# ospi160.net
KiCad netlist of a schematic drawn in EAGLE
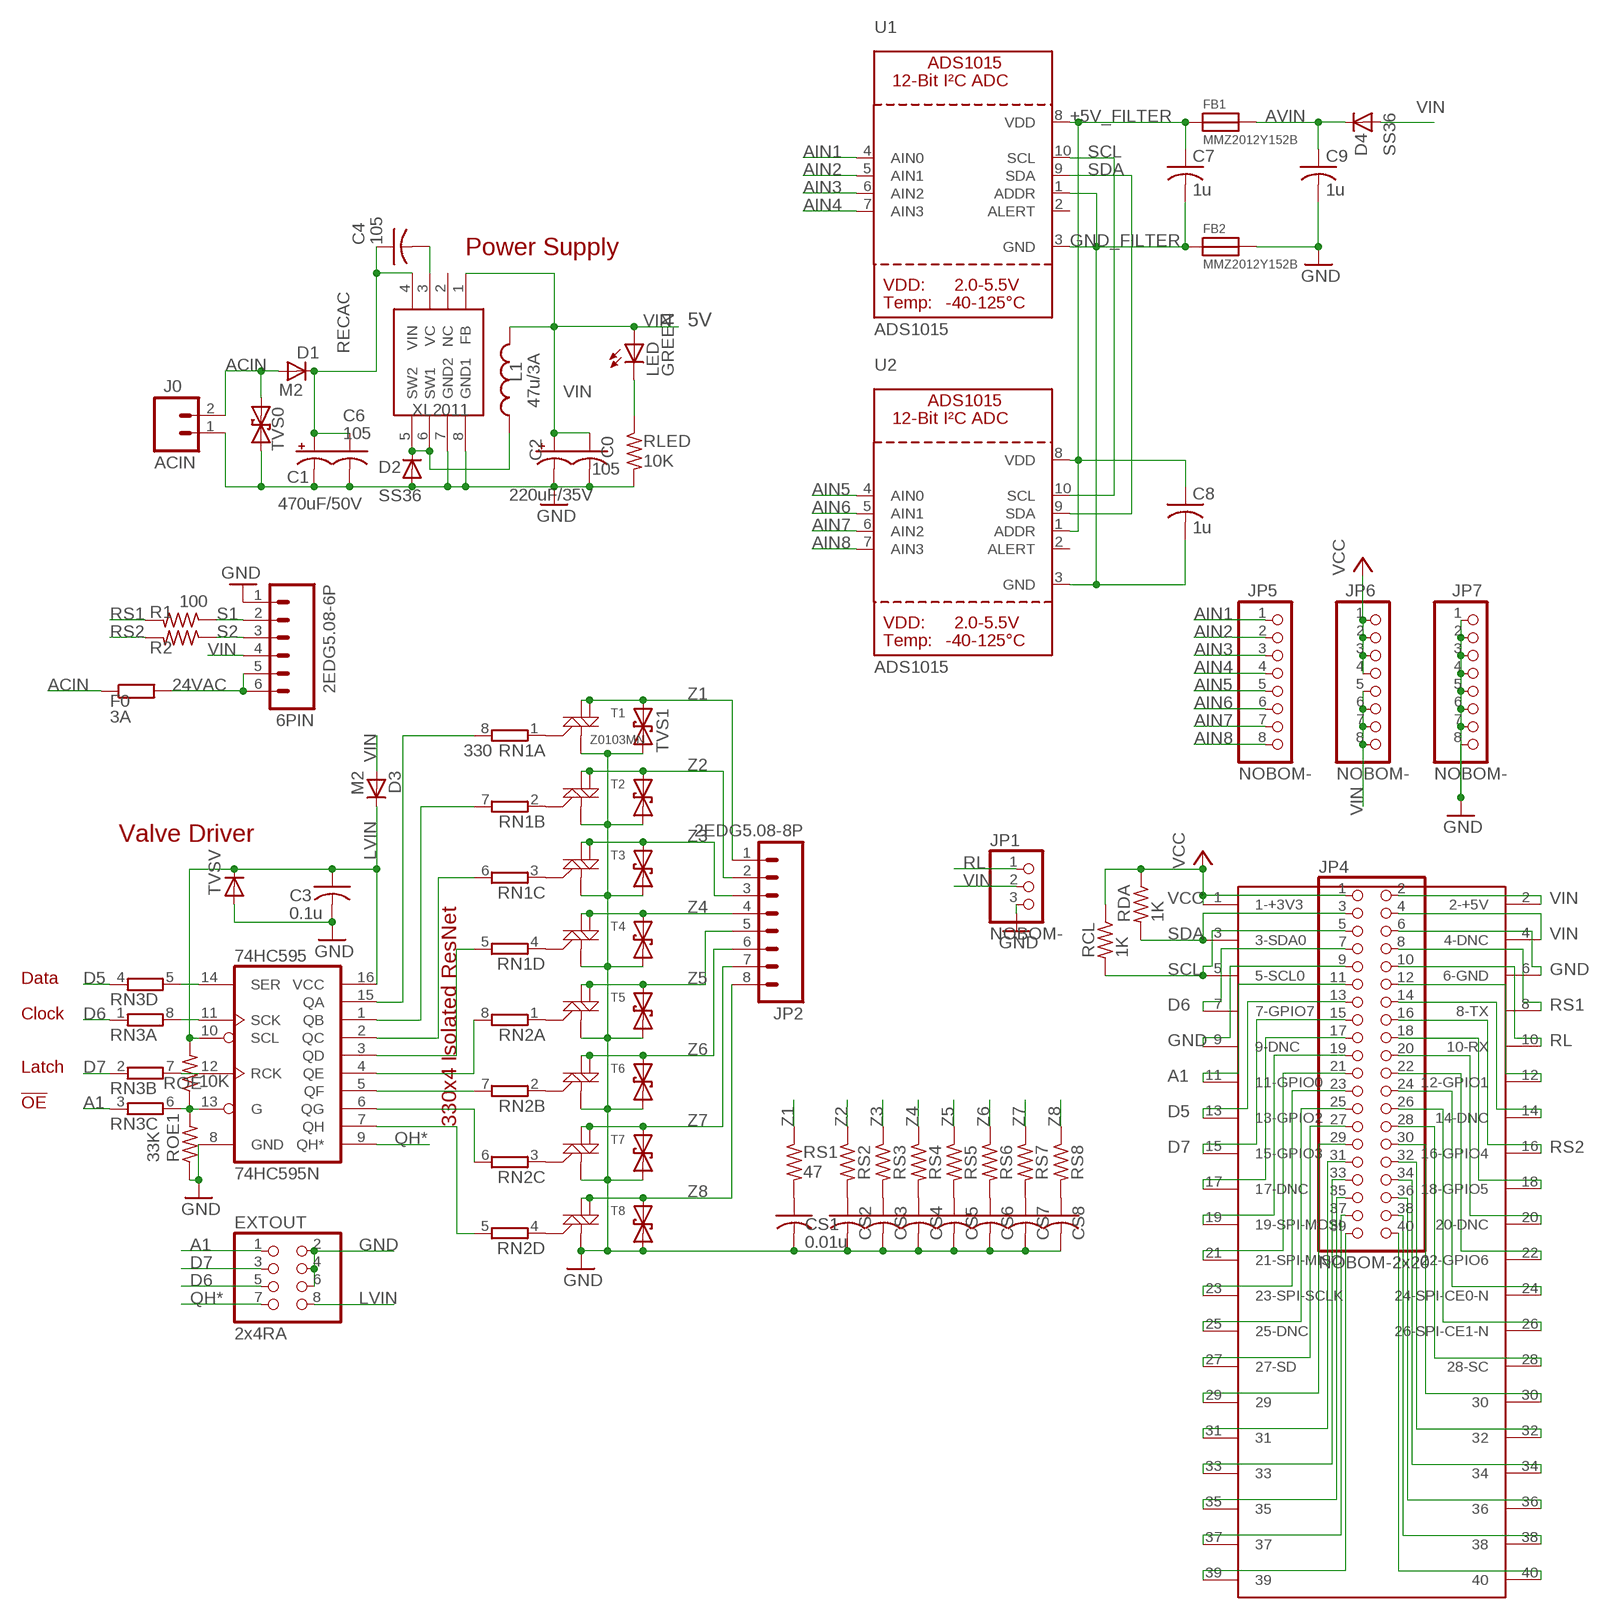
[diagram p0: schematic, sheet 1]

(export (version "E")
  (design (tool "Eeschema 10.0.6"))
  (components
    (comp (ref "6PIN")
      (value "2EDG5.08-6P")
      (footprint "eagle-import:SCREWTERMINAL-5MM-6")
      (libsource (lib "eagle-import") (part "M065MM"))
    )
    (comp (ref "74HC595")
      (value "74HC595N")
      (footprint "eagle-import:SO16")
      (libsource (lib "eagle-import") (part "74595DLS"))
    )
    (comp (ref "C0")
      (value "105")
      (footprint "eagle-import:C0603K")
      (libsource (lib "eagle-import") (part "C-USC0603K"))
    )
    (comp (ref "C1")
      (value "470uF/50V")
      (footprint "eagle-import:E5-10,5")
      (libsource (lib "eagle-import") (part "CPOL-USE5-10.5"))
    )
    (comp (ref "C2")
      (value "220uF/35V")
      (footprint "eagle-import:E3,5-8")
      (libsource (lib "eagle-import") (part "CPOL-USE3.5-8"))
    )
    (comp (ref "C3")
      (value "0.1u")
      (footprint "eagle-import:C0603K")
      (libsource (lib "eagle-import") (part "C-USC0603K"))
    )
    (comp (ref "C4")
      (value "105")
      (footprint "eagle-import:C0603K")
      (libsource (lib "eagle-import") (part "C-USC0603K"))
    )
    (comp (ref "C6")
      (value "105")
      (footprint "eagle-import:C0603K")
      (libsource (lib "eagle-import") (part "C-USC0603K"))
    )
    (comp (ref "C7")
      (value "1u")
      (footprint "eagle-import:C0603K")
      (libsource (lib "eagle-import") (part "adafruit2013_C-USC0603K"))
    )
    (comp (ref "C8")
      (value "1u")
      (footprint "eagle-import:C0603K")
      (libsource (lib "eagle-import") (part "adafruit2013_C-USC0603K"))
    )
    (comp (ref "C9")
      (value "1u")
      (footprint "eagle-import:C0603K")
      (libsource (lib "eagle-import") (part "adafruit2013_C-USC0603K"))
    )
    (comp (ref "CS1")
      (value "0.01u")
      (footprint "eagle-import:C0603K")
      (libsource (lib "eagle-import") (part "C-USC0603K"))
    )
    (comp (ref "CS2")
      (value "0.01u")
      (footprint "eagle-import:C0603K")
      (libsource (lib "eagle-import") (part "C-USC0603K"))
    )
    (comp (ref "CS3")
      (value "0.01u")
      (footprint "eagle-import:C0603K")
      (libsource (lib "eagle-import") (part "C-USC0603K"))
    )
    (comp (ref "CS4")
      (value "0.01u")
      (footprint "eagle-import:C0603K")
      (libsource (lib "eagle-import") (part "C-USC0603K"))
    )
    (comp (ref "CS5")
      (value "0.01u")
      (footprint "eagle-import:C0603K")
      (libsource (lib "eagle-import") (part "C-USC0603K"))
    )
    (comp (ref "CS6")
      (value "0.01u")
      (footprint "eagle-import:C0603K")
      (libsource (lib "eagle-import") (part "C-USC0603K"))
    )
    (comp (ref "CS7")
      (value "0.01u")
      (footprint "eagle-import:C0603K")
      (libsource (lib "eagle-import") (part "C-USC0603K"))
    )
    (comp (ref "CS8")
      (value "0.01u")
      (footprint "eagle-import:C0603K")
      (libsource (lib "eagle-import") (part "C-USC0603K"))
    )
    (comp (ref "D1")
      (value "M2")
      (footprint "eagle-import:DO-214AC")
      (libsource (lib "eagle-import") (part "DIODE-DO-214AC"))
    )
    (comp (ref "D2")
      (value "SS36")
      (footprint "eagle-import:SMB")
      (libsource (lib "eagle-import") (part "DIODE-SMB"))
    )
    (comp (ref "D3")
      (value "M2")
      (footprint "eagle-import:DO-214AC")
      (libsource (lib "eagle-import") (part "DIODE-DO-214AC"))
    )
    (comp (ref "D4")
      (value "SS36")
      (footprint "eagle-import:SMB")
      (libsource (lib "eagle-import") (part "DIODE-SMB"))
    )
    (comp (ref "EXTOUT")
      (value "2x4RA")
      (footprint "eagle-import:2X04_90")
      (libsource (lib "eagle-import") (part "PINHD-2X4/90"))
    )
    (comp (ref "F0")
      (value "3A")
      (footprint "eagle-import:0207_15")
      (libsource (lib "eagle-import") (part "R-EU_0207/15"))
    )
    (comp (ref "FB1")
      (value "MMZ2012Y152B")
      (footprint "eagle-import:0805")
      (libsource (lib "eagle-import") (part "FERRITE0805"))
    )
    (comp (ref "FB2")
      (value "MMZ2012Y152B")
      (footprint "eagle-import:0805")
      (libsource (lib "eagle-import") (part "FERRITE0805"))
    )
    (comp (ref "J0")
      (value "ACIN")
      (footprint "eagle-import:SCREWTERMINAL-4MM-2-X")
      (libsource (lib "eagle-import") (part "M024MM-X"))
    )
    (comp (ref "JP1")
      (value "NOBOM-")
      (footprint "eagle-import:1X03")
      (libsource (lib "eagle-import") (part "PINHD-1X3"))
    )
    (comp (ref "JP2")
      (value "2EDG5.08-8P")
      (footprint "eagle-import:SCREWTERMINAL-5MM-8")
      (libsource (lib "eagle-import") (part "M085MM-8"))
    )
    (comp (ref "JP4")
      (value "NOBOM-2x20")
      (footprint "eagle-import:2X20")
      (libsource (lib "eagle-import") (part "PINHD-2X20"))
    )
    (comp (ref "JP5")
      (value "NOBOM-")
      (footprint "eagle-import:1X08-CLEANBIG")
      (libsource (lib "eagle-import") (part "PINHD-1X8CLEANBIG"))
    )
    (comp (ref "JP6")
      (value "NOBOM-")
      (footprint "eagle-import:1X08-CLEANBIG")
      (libsource (lib "eagle-import") (part "PINHD-1X8CLEANBIG"))
    )
    (comp (ref "JP7")
      (value "NOBOM-")
      (footprint "eagle-import:1X08-CLEANBIG")
      (libsource (lib "eagle-import") (part "PINHD-1X8CLEANBIG"))
    )
    (comp (ref "L1")
      (value "47u/3A")
      (footprint "eagle-import:YT1014")
      (libsource (lib "eagle-import") (part "INDUCTORYT1014"))
    )
    (comp (ref "LED")
      (value "GREEN")
      (footprint "eagle-import:CHIPLED_0805")
      (libsource (lib "eagle-import") (part "LEDCHIPLED_0805"))
    )
    (comp (ref "R1")
      (value "100")
      (footprint "eagle-import:R0603")
      (libsource (lib "eagle-import") (part "R-US_R0603"))
    )
    (comp (ref "R2")
      (value "100")
      (footprint "eagle-import:R0603")
      (libsource (lib "eagle-import") (part "R-US_R0603"))
    )
    (comp (ref "RCL")
      (value "1K")
      (footprint "eagle-import:R0603")
      (libsource (lib "eagle-import") (part "R-US_R0603"))
    )
    (comp (ref "RDA")
      (value "1K")
      (footprint "eagle-import:R0603")
      (libsource (lib "eagle-import") (part "R-US_R0603"))
    )
    (comp (ref "RLED")
      (value "10K")
      (footprint "eagle-import:R0603")
      (libsource (lib "eagle-import") (part "R-US_R0603"))
    )
    (comp (ref "RN1")
      (value "330")
      (footprint "eagle-import:EXB38V")
      (libsource (lib "eagle-import") (part "4R-NEXB38V"))
    )
    (comp (ref "RN2")
      (value "330")
      (footprint "eagle-import:EXB38V")
      (libsource (lib "eagle-import") (part "4R-NEXB38V"))
    )
    (comp (ref "RN3")
      (value "330")
      (footprint "eagle-import:EXB38V")
      (libsource (lib "eagle-import") (part "4R-NEXB38V"))
    )
    (comp (ref "ROE")
      (value "10K")
      (footprint "eagle-import:R0603")
      (libsource (lib "eagle-import") (part "R-US_R0603"))
    )
    (comp (ref "ROE1")
      (value "33K")
      (footprint "eagle-import:R0603")
      (libsource (lib "eagle-import") (part "R-US_R0603"))
    )
    (comp (ref "RPI")
      (value "RPIB+B+")
      (footprint "eagle-import:RPIB+")
      (libsource (lib "eagle-import") (part "RPIB+B+"))
    )
    (comp (ref "RS1")
      (value "47")
      (footprint "eagle-import:R0603")
      (libsource (lib "eagle-import") (part "R-US_R0603"))
    )
    (comp (ref "RS2")
      (value "47")
      (footprint "eagle-import:R0603")
      (libsource (lib "eagle-import") (part "R-US_R0603"))
    )
    (comp (ref "RS3")
      (value "47")
      (footprint "eagle-import:R0603")
      (libsource (lib "eagle-import") (part "R-US_R0603"))
    )
    (comp (ref "RS4")
      (value "47")
      (footprint "eagle-import:R0603")
      (libsource (lib "eagle-import") (part "R-US_R0603"))
    )
    (comp (ref "RS5")
      (value "47")
      (footprint "eagle-import:R0603")
      (libsource (lib "eagle-import") (part "R-US_R0603"))
    )
    (comp (ref "RS6")
      (value "47")
      (footprint "eagle-import:R0603")
      (libsource (lib "eagle-import") (part "R-US_R0603"))
    )
    (comp (ref "RS7")
      (value "47")
      (footprint "eagle-import:R0603")
      (libsource (lib "eagle-import") (part "R-US_R0603"))
    )
    (comp (ref "RS8")
      (value "47")
      (footprint "eagle-import:R0603")
      (libsource (lib "eagle-import") (part "R-US_R0603"))
    )
    (comp (ref "T1")
      (value "Z0103MN")
      (footprint "eagle-import:SOT223")
      (libsource (lib "eagle-import") (part "MAC97SOT223"))
    )
    (comp (ref "T2")
      (value "Z0103MN")
      (footprint "eagle-import:SOT223")
      (libsource (lib "eagle-import") (part "MAC97SOT223"))
    )
    (comp (ref "T3")
      (value "Z0103MN")
      (footprint "eagle-import:SOT223")
      (libsource (lib "eagle-import") (part "MAC97SOT223"))
    )
    (comp (ref "T4")
      (value "Z0103MN")
      (footprint "eagle-import:SOT223")
      (libsource (lib "eagle-import") (part "MAC97SOT223"))
    )
    (comp (ref "T5")
      (value "Z0103MN")
      (footprint "eagle-import:SOT223")
      (libsource (lib "eagle-import") (part "MAC97SOT223"))
    )
    (comp (ref "T6")
      (value "Z0103MN")
      (footprint "eagle-import:SOT223")
      (libsource (lib "eagle-import") (part "MAC97SOT223"))
    )
    (comp (ref "T7")
      (value "Z0103MN")
      (footprint "eagle-import:SOT223")
      (libsource (lib "eagle-import") (part "MAC97SOT223"))
    )
    (comp (ref "T8")
      (value "Z0103MN")
      (footprint "eagle-import:SOT223")
      (libsource (lib "eagle-import") (part "MAC97SOT223"))
    )
    (comp (ref "TVS0")
      (value "TVSSMB")
      (footprint "eagle-import:SMB")
      (libsource (lib "eagle-import") (part "TVSSMB"))
    )
    (comp (ref "TVS1")
      (value "SMBJ43CA")
      (footprint "eagle-import:SMB")
      (libsource (lib "eagle-import") (part "TVSSMB"))
    )
    (comp (ref "TVS2")
      (value "SMBJ43CA")
      (footprint "eagle-import:SMB")
      (libsource (lib "eagle-import") (part "TVSSMB"))
    )
    (comp (ref "TVS3")
      (value "SMBJ43CA")
      (footprint "eagle-import:SMB")
      (libsource (lib "eagle-import") (part "TVSSMB"))
    )
    (comp (ref "TVS4")
      (value "SMBJ43CA")
      (footprint "eagle-import:SMB")
      (libsource (lib "eagle-import") (part "TVSSMB"))
    )
    (comp (ref "TVS5")
      (value "SMBJ43CA")
      (footprint "eagle-import:SMB")
      (libsource (lib "eagle-import") (part "TVSSMB"))
    )
    (comp (ref "TVS6")
      (value "SMBJ43CA")
      (footprint "eagle-import:SMB")
      (libsource (lib "eagle-import") (part "TVSSMB"))
    )
    (comp (ref "TVS7")
      (value "SMBJ43CA")
      (footprint "eagle-import:SMB")
      (libsource (lib "eagle-import") (part "TVSSMB"))
    )
    (comp (ref "TVS8")
      (value "SMBJ43CA")
      (footprint "eagle-import:SMB")
      (libsource (lib "eagle-import") (part "TVSSMB"))
    )
    (comp (ref "TVSV")
      (value "SMBJ5.0A")
      (footprint "eagle-import:SMA-DIODE_ALT")
      (libsource (lib "eagle-import") (part "DIODESMA-ALT"))
    )
    (comp (ref "U1")
      (value "ADS1015")
      (footprint "eagle-import:MSOP10")
      (libsource (lib "eagle-import") (part "ADC_ADS1015"))
    )
    (comp (ref "U2")
      (value "ADS1015")
      (footprint "eagle-import:MSOP10")
      (libsource (lib "eagle-import") (part "ADC_ADS1015"))
    )
    (comp (ref "XL2011")
      (value "XL2011")
      (footprint "eagle-import:SO08")
      (libsource (lib "eagle-import") (part "XL2001"))
    )
  )
  (nets
    (net (code "1") (name "/+5V_FILTER") (class "Default")
      (node (ref "C7") (pin "1") (pinfunction "1_1") (pintype "passive"))
      (node (ref "C8") (pin "1") (pinfunction "1_1") (pintype "passive"))
      (node (ref "FB1") (pin "1") (pinfunction "P$1_1") (pintype "bidirectional"))
      (node (ref "U1") (pin "8") (pinfunction "VDD_8") (pintype "bidirectional"))
      (node (ref "U2") (pin "1") (pinfunction "ADDR_1") (pintype "bidirectional"))
      (node (ref "U2") (pin "8") (pinfunction "VDD_8") (pintype "bidirectional"))
    )
    (net (code "2") (name "/24VAC") (class "Default")
      (node (ref "6PIN") (pin "5") (pinfunction "5_5") (pintype "passive"))
      (node (ref "6PIN") (pin "6") (pinfunction "6_6") (pintype "passive"))
      (node (ref "F0") (pin "2") (pinfunction "2_2") (pintype "passive"))
    )
    (net (code "3") (name "/A1") (class "Default")
      (node (ref "EXTOUT") (pin "1") (pinfunction "1_1") (pintype "passive"))
      (node (ref "JP4") (pin "11") (pinfunction "11_11") (pintype "passive"))
      (node (ref "RN3") (pin "3") (pinfunction "1_3") (pintype "passive"))
      (node (ref "RPI") (pin "11") (pinfunction "11-GPIO0_11") (pintype "bidirectional"))
    )
    (net (code "4") (name "/ACIN") (class "Default")
      (node (ref "D1") (pin "A") (pinfunction "A_A") (pintype "passive"))
      (node (ref "F0") (pin "1") (pinfunction "1_1") (pintype "passive"))
      (node (ref "J0") (pin "2") (pinfunction "2_2") (pintype "passive"))
      (node (ref "TVS0") (pin "C") (pinfunction "C_C") (pintype "passive"))
    )
    (net (code "5") (name "/AIN1") (class "Default")
      (node (ref "JP5") (pin "1") (pinfunction "1_1") (pintype "passive"))
      (node (ref "U1") (pin "4") (pinfunction "AIN0_4") (pintype "bidirectional"))
    )
    (net (code "6") (name "/AIN2") (class "Default")
      (node (ref "JP5") (pin "2") (pinfunction "2_2") (pintype "passive"))
      (node (ref "U1") (pin "5") (pinfunction "AIN1_5") (pintype "bidirectional"))
    )
    (net (code "7") (name "/AIN3") (class "Default")
      (node (ref "JP5") (pin "3") (pinfunction "3_3") (pintype "passive"))
      (node (ref "U1") (pin "6") (pinfunction "AIN2_6") (pintype "bidirectional"))
    )
    (net (code "8") (name "/AIN4") (class "Default")
      (node (ref "JP5") (pin "4") (pinfunction "4_4") (pintype "passive"))
      (node (ref "U1") (pin "7") (pinfunction "AIN3_7") (pintype "bidirectional"))
    )
    (net (code "9") (name "/AIN5") (class "Default")
      (node (ref "JP5") (pin "5") (pinfunction "5_5") (pintype "passive"))
      (node (ref "U2") (pin "4") (pinfunction "AIN0_4") (pintype "bidirectional"))
    )
    (net (code "10") (name "/AIN6") (class "Default")
      (node (ref "JP5") (pin "6") (pinfunction "6_6") (pintype "passive"))
      (node (ref "U2") (pin "5") (pinfunction "AIN1_5") (pintype "bidirectional"))
    )
    (net (code "11") (name "/AIN7") (class "Default")
      (node (ref "JP5") (pin "7") (pinfunction "7_7") (pintype "passive"))
      (node (ref "U2") (pin "6") (pinfunction "AIN2_6") (pintype "bidirectional"))
    )
    (net (code "12") (name "/AIN8") (class "Default")
      (node (ref "JP5") (pin "8") (pinfunction "8_8") (pintype "passive"))
      (node (ref "U2") (pin "7") (pinfunction "AIN3_7") (pintype "bidirectional"))
    )
    (net (code "13") (name "/AVIN") (class "Default")
      (node (ref "C9") (pin "1") (pinfunction "1_1") (pintype "passive"))
      (node (ref "D4") (pin "C") (pinfunction "C_C") (pintype "passive"))
      (node (ref "FB1") (pin "2") (pinfunction "P$2_2") (pintype "bidirectional"))
    )
    (net (code "14") (name "/D5") (class "Default")
      (node (ref "JP4") (pin "13") (pinfunction "13_13") (pintype "passive"))
      (node (ref "RN3") (pin "4") (pinfunction "1_4") (pintype "passive"))
      (node (ref "RPI") (pin "13") (pinfunction "13-GPIO2_13") (pintype "bidirectional"))
    )
    (net (code "15") (name "/D6") (class "Default")
      (node (ref "EXTOUT") (pin "5") (pinfunction "5_5") (pintype "passive"))
      (node (ref "JP4") (pin "7") (pinfunction "7_7") (pintype "passive"))
      (node (ref "RN3") (pin "1") (pinfunction "1_1") (pintype "passive"))
      (node (ref "RPI") (pin "7") (pinfunction "7-GPIO7_7") (pintype "bidirectional"))
    )
    (net (code "16") (name "/D7") (class "Default")
      (node (ref "EXTOUT") (pin "3") (pinfunction "3_3") (pintype "passive"))
      (node (ref "JP4") (pin "15") (pinfunction "15_15") (pintype "passive"))
      (node (ref "RN3") (pin "2") (pinfunction "1_2") (pintype "passive"))
      (node (ref "RPI") (pin "15") (pinfunction "15-GPIO3_15") (pintype "bidirectional"))
    )
    (net (code "17") (name "/GND_FILTER") (class "Default")
      (node (ref "C7") (pin "2") (pinfunction "2_2") (pintype "passive"))
      (node (ref "C8") (pin "2") (pinfunction "2_2") (pintype "passive"))
      (node (ref "FB2") (pin "1") (pinfunction "P$1_1") (pintype "bidirectional"))
      (node (ref "U1") (pin "1") (pinfunction "ADDR_1") (pintype "bidirectional"))
      (node (ref "U1") (pin "3") (pinfunction "GND_3") (pintype "bidirectional"))
      (node (ref "U2") (pin "3") (pinfunction "GND_3") (pintype "bidirectional"))
    )
    (net (code "18") (name "/LVIN") (class "Default")
      (node (ref "74HC595") (pin "10") (pinfunction "SCL_10") (pintype "input"))
      (node (ref "74HC595") (pin "16") (pinfunction "VCC_16") (pintype "power_in"))
      (node (ref "C3") (pin "1") (pinfunction "1_1") (pintype "passive"))
      (node (ref "D3") (pin "C") (pinfunction "C_C") (pintype "passive"))
      (node (ref "EXTOUT") (pin "8") (pinfunction "8_8") (pintype "passive"))
      (node (ref "ROE") (pin "2") (pinfunction "2_2") (pintype "passive"))
      (node (ref "TVSV") (pin "C") (pinfunction "C_C") (pintype "passive"))
    )
    (net (code "19") (name "/QH*") (class "Default")
      (node (ref "74HC595") (pin "9") (pinfunction "QH*_9") (pintype "tri_state"))
      (node (ref "EXTOUT") (pin "7") (pinfunction "7_7") (pintype "passive"))
    )
    (net (code "20") (name "/RECAC") (class "Default")
      (node (ref "C1") (pin "+") (pinfunction "+_+") (pintype "passive"))
      (node (ref "C4") (pin "1") (pinfunction "1_1") (pintype "passive"))
      (node (ref "C6") (pin "1") (pinfunction "1_1") (pintype "passive"))
      (node (ref "D1") (pin "C") (pinfunction "C_C") (pintype "passive"))
      (node (ref "XL2011") (pin "4") (pinfunction "VIN_4") (pintype "bidirectional"))
    )
    (net (code "21") (name "/RL") (class "Default")
      (node (ref "JP1") (pin "1") (pinfunction "1_1") (pintype "passive"))
      (node (ref "JP4") (pin "10") (pinfunction "10_10") (pintype "passive"))
      (node (ref "RPI") (pin "10") (pinfunction "10-RX_10") (pintype "bidirectional"))
    )
    (net (code "22") (name "/RS1") (class "Default")
      (node (ref "JP4") (pin "8") (pinfunction "8_8") (pintype "passive"))
      (node (ref "R1") (pin "2") (pinfunction "2_2") (pintype "passive"))
      (node (ref "RPI") (pin "8") (pinfunction "8-TX_8") (pintype "bidirectional"))
    )
    (net (code "23") (name "/RS2") (class "Default")
      (node (ref "JP4") (pin "16") (pinfunction "16_16") (pintype "passive"))
      (node (ref "R2") (pin "2") (pinfunction "2_2") (pintype "passive"))
      (node (ref "RPI") (pin "16") (pinfunction "16-GPIO4_16") (pintype "bidirectional"))
    )
    (net (code "24") (name "/S1") (class "Default")
      (node (ref "6PIN") (pin "2") (pinfunction "2_2") (pintype "passive"))
      (node (ref "R1") (pin "1") (pinfunction "1_1") (pintype "passive"))
    )
    (net (code "25") (name "/S2") (class "Default")
      (node (ref "6PIN") (pin "3") (pinfunction "3_3") (pintype "passive"))
      (node (ref "R2") (pin "1") (pinfunction "1_1") (pintype "passive"))
    )
    (net (code "26") (name "/SCL") (class "Default")
      (node (ref "JP4") (pin "5") (pinfunction "5_5") (pintype "passive"))
      (node (ref "RCL") (pin "2") (pinfunction "2_2") (pintype "passive"))
      (node (ref "RPI") (pin "5") (pinfunction "5-SCL0_5") (pintype "bidirectional"))
      (node (ref "U1") (pin "10") (pinfunction "SCL_10") (pintype "bidirectional"))
      (node (ref "U2") (pin "10") (pinfunction "SCL_10") (pintype "bidirectional"))
    )
    (net (code "27") (name "/SDA") (class "Default")
      (node (ref "JP4") (pin "3") (pinfunction "3_3") (pintype "passive"))
      (node (ref "RDA") (pin "2") (pinfunction "2_2") (pintype "passive"))
      (node (ref "RPI") (pin "3") (pinfunction "3-SDA0_3") (pintype "bidirectional"))
      (node (ref "U1") (pin "9") (pinfunction "SDA_9") (pintype "bidirectional"))
      (node (ref "U2") (pin "9") (pinfunction "SDA_9") (pintype "bidirectional"))
    )
    (net (code "28") (name "/VIN") (class "Default")
      (node (ref "6PIN") (pin "4") (pinfunction "4_4") (pintype "passive"))
      (node (ref "C0") (pin "1") (pinfunction "1_1") (pintype "passive"))
      (node (ref "C2") (pin "+") (pinfunction "+_+") (pintype "passive"))
      (node (ref "D3") (pin "A") (pinfunction "A_A") (pintype "passive"))
      (node (ref "D4") (pin "A") (pinfunction "A_A") (pintype "passive"))
      (node (ref "JP1") (pin "2") (pinfunction "2_2") (pintype "passive"))
      (node (ref "JP4") (pin "2") (pinfunction "2_2") (pintype "passive"))
      (node (ref "JP4") (pin "4") (pinfunction "4_4") (pintype "passive"))
      (node (ref "JP6") (pin "5") (pinfunction "5_5") (pintype "passive"))
      (node (ref "JP6") (pin "6") (pinfunction "6_6") (pintype "passive"))
      (node (ref "JP6") (pin "7") (pinfunction "7_7") (pintype "passive"))
      (node (ref "JP6") (pin "8") (pinfunction "8_8") (pintype "passive"))
      (node (ref "L1") (pin "P$2") (pinfunction "2_P$2") (pintype "passive"))
      (node (ref "LED") (pin "A") (pinfunction "A_A") (pintype "passive"))
      (node (ref "RPI") (pin "2") (pinfunction "2-+5V_2") (pintype "bidirectional"))
      (node (ref "RPI") (pin "4") (pinfunction "4-DNC_4") (pintype "bidirectional"))
      (node (ref "XL2011") (pin "1") (pinfunction "FB_1") (pintype "input"))
    )
    (net (code "29") (name "/Z1") (class "Default")
      (node (ref "JP2") (pin "1") (pinfunction "1_1") (pintype "passive"))
      (node (ref "RS1") (pin "1") (pinfunction "1_1") (pintype "passive"))
      (node (ref "T1") (pin "2") (pinfunction "M2_2") (pintype "bidirectional"))
      (node (ref "T1") (pin "4") (pinfunction "M2-4_4") (pintype "bidirectional"))
      (node (ref "TVS1") (pin "A") (pinfunction "A_A") (pintype "passive"))
    )
    (net (code "30") (name "/Z2") (class "Default")
      (node (ref "JP2") (pin "2") (pinfunction "2_2") (pintype "passive"))
      (node (ref "RS2") (pin "1") (pinfunction "1_1") (pintype "passive"))
      (node (ref "T2") (pin "2") (pinfunction "M2_2") (pintype "bidirectional"))
      (node (ref "T2") (pin "4") (pinfunction "M2-4_4") (pintype "bidirectional"))
      (node (ref "TVS2") (pin "A") (pinfunction "A_A") (pintype "passive"))
    )
    (net (code "31") (name "/Z3") (class "Default")
      (node (ref "JP2") (pin "3") (pinfunction "3_3") (pintype "passive"))
      (node (ref "RS3") (pin "1") (pinfunction "1_1") (pintype "passive"))
      (node (ref "T3") (pin "2") (pinfunction "M2_2") (pintype "bidirectional"))
      (node (ref "T3") (pin "4") (pinfunction "M2-4_4") (pintype "bidirectional"))
      (node (ref "TVS3") (pin "A") (pinfunction "A_A") (pintype "passive"))
    )
    (net (code "32") (name "/Z4") (class "Default")
      (node (ref "JP2") (pin "4") (pinfunction "4_4") (pintype "passive"))
      (node (ref "RS4") (pin "1") (pinfunction "1_1") (pintype "passive"))
      (node (ref "T4") (pin "2") (pinfunction "M2_2") (pintype "bidirectional"))
      (node (ref "T4") (pin "4") (pinfunction "M2-4_4") (pintype "bidirectional"))
      (node (ref "TVS4") (pin "A") (pinfunction "A_A") (pintype "passive"))
    )
    (net (code "33") (name "/Z5") (class "Default")
      (node (ref "JP2") (pin "5") (pinfunction "5_5") (pintype "passive"))
      (node (ref "RS5") (pin "1") (pinfunction "1_1") (pintype "passive"))
      (node (ref "T5") (pin "2") (pinfunction "M2_2") (pintype "bidirectional"))
      (node (ref "T5") (pin "4") (pinfunction "M2-4_4") (pintype "bidirectional"))
      (node (ref "TVS5") (pin "A") (pinfunction "A_A") (pintype "passive"))
    )
    (net (code "34") (name "/Z6") (class "Default")
      (node (ref "JP2") (pin "6") (pinfunction "6_6") (pintype "passive"))
      (node (ref "RS6") (pin "1") (pinfunction "1_1") (pintype "passive"))
      (node (ref "T6") (pin "2") (pinfunction "M2_2") (pintype "bidirectional"))
      (node (ref "T6") (pin "4") (pinfunction "M2-4_4") (pintype "bidirectional"))
      (node (ref "TVS6") (pin "A") (pinfunction "A_A") (pintype "passive"))
    )
    (net (code "35") (name "/Z7") (class "Default")
      (node (ref "JP2") (pin "7") (pinfunction "7_7") (pintype "passive"))
      (node (ref "RS7") (pin "1") (pinfunction "1_1") (pintype "passive"))
      (node (ref "T7") (pin "2") (pinfunction "M2_2") (pintype "bidirectional"))
      (node (ref "T7") (pin "4") (pinfunction "M2-4_4") (pintype "bidirectional"))
      (node (ref "TVS7") (pin "A") (pinfunction "A_A") (pintype "passive"))
    )
    (net (code "36") (name "/Z8") (class "Default")
      (node (ref "JP2") (pin "8") (pinfunction "8_8") (pintype "passive"))
      (node (ref "RS8") (pin "1") (pinfunction "1_1") (pintype "passive"))
      (node (ref "T8") (pin "2") (pinfunction "M2_2") (pintype "bidirectional"))
      (node (ref "T8") (pin "4") (pinfunction "M2-4_4") (pintype "bidirectional"))
      (node (ref "TVS8") (pin "A") (pinfunction "A_A") (pintype "passive"))
    )
    (net (code "37") (name "GND") (class "Default")
      (node (ref "6PIN") (pin "1") (pinfunction "1_1") (pintype "passive"))
      (node (ref "74HC595") (pin "8") (pinfunction "GND_8") (pintype "power_in"))
      (node (ref "C0") (pin "2") (pinfunction "2_2") (pintype "passive"))
      (node (ref "C1") (pin "-") (pinfunction "-_-") (pintype "passive"))
      (node (ref "C2") (pin "-") (pinfunction "-_-") (pintype "passive"))
      (node (ref "C3") (pin "2") (pinfunction "2_2") (pintype "passive"))
      (node (ref "C6") (pin "2") (pinfunction "2_2") (pintype "passive"))
      (node (ref "C9") (pin "2") (pinfunction "2_2") (pintype "passive"))
      (node (ref "CS1") (pin "2") (pinfunction "2_2") (pintype "passive"))
      (node (ref "CS2") (pin "2") (pinfunction "2_2") (pintype "passive"))
      (node (ref "CS3") (pin "2") (pinfunction "2_2") (pintype "passive"))
      (node (ref "CS4") (pin "2") (pinfunction "2_2") (pintype "passive"))
      (node (ref "CS5") (pin "2") (pinfunction "2_2") (pintype "passive"))
      (node (ref "CS6") (pin "2") (pinfunction "2_2") (pintype "passive"))
      (node (ref "CS7") (pin "2") (pinfunction "2_2") (pintype "passive"))
      (node (ref "CS8") (pin "2") (pinfunction "2_2") (pintype "passive"))
      (node (ref "D2") (pin "A") (pinfunction "A_A") (pintype "passive"))
      (node (ref "EXTOUT") (pin "2") (pinfunction "2_2") (pintype "passive"))
      (node (ref "EXTOUT") (pin "4") (pinfunction "4_4") (pintype "passive"))
      (node (ref "EXTOUT") (pin "6") (pinfunction "6_6") (pintype "passive"))
      (node (ref "FB2") (pin "2") (pinfunction "P$2_2") (pintype "bidirectional"))
      (node (ref "J0") (pin "1") (pinfunction "1_1") (pintype "passive"))
      (node (ref "JP1") (pin "3") (pinfunction "3_3") (pintype "passive"))
      (node (ref "JP4") (pin "6") (pinfunction "6_6") (pintype "passive"))
      (node (ref "JP4") (pin "9") (pinfunction "9_9") (pintype "passive"))
      (node (ref "JP7") (pin "1") (pinfunction "1_1") (pintype "passive"))
      (node (ref "JP7") (pin "2") (pinfunction "2_2") (pintype "passive"))
      (node (ref "JP7") (pin "3") (pinfunction "3_3") (pintype "passive"))
      (node (ref "JP7") (pin "4") (pinfunction "4_4") (pintype "passive"))
      (node (ref "JP7") (pin "5") (pinfunction "5_5") (pintype "passive"))
      (node (ref "JP7") (pin "6") (pinfunction "6_6") (pintype "passive"))
      (node (ref "JP7") (pin "7") (pinfunction "7_7") (pintype "passive"))
      (node (ref "JP7") (pin "8") (pinfunction "8_8") (pintype "passive"))
      (node (ref "RLED") (pin "2") (pinfunction "2_2") (pintype "passive"))
      (node (ref "ROE1") (pin "1") (pinfunction "1_1") (pintype "passive"))
      (node (ref "RPI") (pin "6") (pinfunction "6-GND_6") (pintype "bidirectional"))
      (node (ref "RPI") (pin "9") (pinfunction "9-DNC_9") (pintype "bidirectional"))
      (node (ref "T1") (pin "1") (pinfunction "M1_1") (pintype "bidirectional"))
      (node (ref "T2") (pin "1") (pinfunction "M1_1") (pintype "bidirectional"))
      (node (ref "T3") (pin "1") (pinfunction "M1_1") (pintype "bidirectional"))
      (node (ref "T4") (pin "1") (pinfunction "M1_1") (pintype "bidirectional"))
      (node (ref "T5") (pin "1") (pinfunction "M1_1") (pintype "bidirectional"))
      (node (ref "T6") (pin "1") (pinfunction "M1_1") (pintype "bidirectional"))
      (node (ref "T7") (pin "1") (pinfunction "M1_1") (pintype "bidirectional"))
      (node (ref "T8") (pin "1") (pinfunction "M1_1") (pintype "bidirectional"))
      (node (ref "TVS0") (pin "A") (pinfunction "A_A") (pintype "passive"))
      (node (ref "TVS1") (pin "C") (pinfunction "C_C") (pintype "passive"))
      (node (ref "TVS2") (pin "C") (pinfunction "C_C") (pintype "passive"))
      (node (ref "TVS3") (pin "C") (pinfunction "C_C") (pintype "passive"))
      (node (ref "TVS4") (pin "C") (pinfunction "C_C") (pintype "passive"))
      (node (ref "TVS5") (pin "C") (pinfunction "C_C") (pintype "passive"))
      (node (ref "TVS6") (pin "C") (pinfunction "C_C") (pintype "passive"))
      (node (ref "TVS7") (pin "C") (pinfunction "C_C") (pintype "passive"))
      (node (ref "TVS8") (pin "C") (pinfunction "C_C") (pintype "passive"))
      (node (ref "TVSV") (pin "A") (pinfunction "A_A") (pintype "passive"))
      (node (ref "XL2011") (pin "7") (pinfunction "GND2_7") (pintype "power_in"))
      (node (ref "XL2011") (pin "8") (pinfunction "GND1_8") (pintype "power_in"))
    )
    (net (code "38") (name "Net-(74HC595-G)") (class "Default")
      (node (ref "74HC595") (pin "13") (pinfunction "G_13") (pintype "input"))
      (node (ref "RN3") (pin "6") (pinfunction "2_6") (pintype "passive"))
      (node (ref "ROE") (pin "1") (pinfunction "1_1") (pintype "passive"))
      (node (ref "ROE1") (pin "2") (pinfunction "2_2") (pintype "passive"))
    )
    (net (code "39") (name "Net-(74HC595-QA)") (class "Default")
      (node (ref "74HC595") (pin "15") (pinfunction "QA_15") (pintype "tri_state"))
      (node (ref "RN1") (pin "8") (pinfunction "2_8") (pintype "passive"))
    )
    (net (code "40") (name "Net-(74HC595-QB)") (class "Default")
      (node (ref "74HC595") (pin "1") (pinfunction "QB_1") (pintype "tri_state"))
      (node (ref "RN1") (pin "7") (pinfunction "2_7") (pintype "passive"))
    )
    (net (code "41") (name "Net-(74HC595-QC)") (class "Default")
      (node (ref "74HC595") (pin "2") (pinfunction "QC_2") (pintype "tri_state"))
      (node (ref "RN1") (pin "6") (pinfunction "2_6") (pintype "passive"))
    )
    (net (code "42") (name "Net-(74HC595-QD)") (class "Default")
      (node (ref "74HC595") (pin "3") (pinfunction "QD_3") (pintype "tri_state"))
      (node (ref "RN1") (pin "5") (pinfunction "2_5") (pintype "passive"))
    )
    (net (code "43") (name "Net-(74HC595-QE)") (class "Default")
      (node (ref "74HC595") (pin "4") (pinfunction "QE_4") (pintype "tri_state"))
      (node (ref "RN2") (pin "8") (pinfunction "2_8") (pintype "passive"))
    )
    (net (code "44") (name "Net-(74HC595-QF)") (class "Default")
      (node (ref "74HC595") (pin "5") (pinfunction "QF_5") (pintype "tri_state"))
      (node (ref "RN2") (pin "7") (pinfunction "2_7") (pintype "passive"))
    )
    (net (code "45") (name "Net-(74HC595-QG)") (class "Default")
      (node (ref "74HC595") (pin "6") (pinfunction "QG_6") (pintype "tri_state"))
      (node (ref "RN2") (pin "6") (pinfunction "2_6") (pintype "passive"))
    )
    (net (code "46") (name "Net-(74HC595-QH)") (class "Default")
      (node (ref "74HC595") (pin "7") (pinfunction "QH_7") (pintype "tri_state"))
      (node (ref "RN2") (pin "5") (pinfunction "2_5") (pintype "passive"))
    )
    (net (code "47") (name "Net-(74HC595-RCK)") (class "Default")
      (node (ref "74HC595") (pin "12") (pinfunction "RCK_12") (pintype "input"))
      (node (ref "RN3") (pin "7") (pinfunction "2_7") (pintype "passive"))
    )
    (net (code "48") (name "Net-(74HC595-SCK)") (class "Default")
      (node (ref "74HC595") (pin "11") (pinfunction "SCK_11") (pintype "input"))
      (node (ref "RN3") (pin "8") (pinfunction "2_8") (pintype "passive"))
    )
    (net (code "49") (name "Net-(74HC595-SER)") (class "Default")
      (node (ref "74HC595") (pin "14") (pinfunction "SER_14") (pintype "input"))
      (node (ref "RN3") (pin "5") (pinfunction "2_5") (pintype "passive"))
    )
    (net (code "50") (name "Net-(CS1-Pad1)") (class "Default")
      (node (ref "CS1") (pin "1") (pinfunction "1_1") (pintype "passive"))
      (node (ref "RS1") (pin "2") (pinfunction "2_2") (pintype "passive"))
    )
    (net (code "51") (name "Net-(CS2-Pad1)") (class "Default")
      (node (ref "CS2") (pin "1") (pinfunction "1_1") (pintype "passive"))
      (node (ref "RS2") (pin "2") (pinfunction "2_2") (pintype "passive"))
    )
    (net (code "52") (name "Net-(CS3-Pad1)") (class "Default")
      (node (ref "CS3") (pin "1") (pinfunction "1_1") (pintype "passive"))
      (node (ref "RS3") (pin "2") (pinfunction "2_2") (pintype "passive"))
    )
    (net (code "53") (name "Net-(CS4-Pad1)") (class "Default")
      (node (ref "CS4") (pin "1") (pinfunction "1_1") (pintype "passive"))
      (node (ref "RS4") (pin "2") (pinfunction "2_2") (pintype "passive"))
    )
    (net (code "54") (name "Net-(CS5-Pad1)") (class "Default")
      (node (ref "CS5") (pin "1") (pinfunction "1_1") (pintype "passive"))
      (node (ref "RS5") (pin "2") (pinfunction "2_2") (pintype "passive"))
    )
    (net (code "55") (name "Net-(CS6-Pad1)") (class "Default")
      (node (ref "CS6") (pin "1") (pinfunction "1_1") (pintype "passive"))
      (node (ref "RS6") (pin "2") (pinfunction "2_2") (pintype "passive"))
    )
    (net (code "56") (name "Net-(CS7-Pad1)") (class "Default")
      (node (ref "CS7") (pin "1") (pinfunction "1_1") (pintype "passive"))
      (node (ref "RS7") (pin "2") (pinfunction "2_2") (pintype "passive"))
    )
    (net (code "57") (name "Net-(CS8-Pad1)") (class "Default")
      (node (ref "CS8") (pin "1") (pinfunction "1_1") (pintype "passive"))
      (node (ref "RS8") (pin "2") (pinfunction "2_2") (pintype "passive"))
    )
    (net (code "58") (name "Net-(JP4-Pad29)") (class "Default")
      (node (ref "JP4") (pin "29") (pinfunction "29_29") (pintype "passive"))
      (node (ref "RPI") (pin "29") (pinfunction "29_29") (pintype "bidirectional"))
    )
    (net (code "59") (name "Net-(JP4-Pad30)") (class "Default")
      (node (ref "JP4") (pin "30") (pinfunction "30_30") (pintype "passive"))
      (node (ref "RPI") (pin "30") (pinfunction "30_30") (pintype "bidirectional"))
    )
    (net (code "60") (name "Net-(JP4-Pad31)") (class "Default")
      (node (ref "JP4") (pin "31") (pinfunction "31_31") (pintype "passive"))
      (node (ref "RPI") (pin "31") (pinfunction "31_31") (pintype "bidirectional"))
    )
    (net (code "61") (name "Net-(JP4-Pad32)") (class "Default")
      (node (ref "JP4") (pin "32") (pinfunction "32_32") (pintype "passive"))
      (node (ref "RPI") (pin "32") (pinfunction "32_32") (pintype "bidirectional"))
    )
    (net (code "62") (name "Net-(JP4-Pad33)") (class "Default")
      (node (ref "JP4") (pin "33") (pinfunction "33_33") (pintype "passive"))
      (node (ref "RPI") (pin "33") (pinfunction "33_33") (pintype "bidirectional"))
    )
    (net (code "63") (name "Net-(JP4-Pad34)") (class "Default")
      (node (ref "JP4") (pin "34") (pinfunction "34_34") (pintype "passive"))
      (node (ref "RPI") (pin "34") (pinfunction "34_34") (pintype "bidirectional"))
    )
    (net (code "64") (name "Net-(JP4-Pad35)") (class "Default")
      (node (ref "JP4") (pin "35") (pinfunction "35_35") (pintype "passive"))
      (node (ref "RPI") (pin "35") (pinfunction "35_35") (pintype "bidirectional"))
    )
    (net (code "65") (name "Net-(JP4-Pad36)") (class "Default")
      (node (ref "JP4") (pin "36") (pinfunction "36_36") (pintype "passive"))
      (node (ref "RPI") (pin "36") (pinfunction "36_36") (pintype "bidirectional"))
    )
    (net (code "66") (name "Net-(JP4-Pad37)") (class "Default")
      (node (ref "JP4") (pin "37") (pinfunction "37_37") (pintype "passive"))
      (node (ref "RPI") (pin "37") (pinfunction "37_37") (pintype "bidirectional"))
    )
    (net (code "67") (name "Net-(JP4-Pad38)") (class "Default")
      (node (ref "JP4") (pin "38") (pinfunction "38_38") (pintype "passive"))
      (node (ref "RPI") (pin "38") (pinfunction "38_38") (pintype "bidirectional"))
    )
    (net (code "68") (name "Net-(JP4-Pad39)") (class "Default")
      (node (ref "JP4") (pin "39") (pinfunction "39_39") (pintype "passive"))
      (node (ref "RPI") (pin "39") (pinfunction "39_39") (pintype "bidirectional"))
    )
    (net (code "69") (name "Net-(JP4-Pad40)") (class "Default")
      (node (ref "JP4") (pin "40") (pinfunction "40_40") (pintype "passive"))
      (node (ref "RPI") (pin "40") (pinfunction "40_40") (pintype "bidirectional"))
    )
    (net (code "70") (name "Net-(L1-1)") (class "Default")
      (node (ref "D2") (pin "C") (pinfunction "C_C") (pintype "passive"))
      (node (ref "L1") (pin "P$1") (pinfunction "1_P$1") (pintype "passive"))
      (node (ref "XL2011") (pin "5") (pinfunction "SW2_5") (pintype "power_in"))
      (node (ref "XL2011") (pin "6") (pinfunction "SW1_6") (pintype "power_in"))
    )
    (net (code "71") (name "Net-(LED-PadC)") (class "Default")
      (node (ref "LED") (pin "C") (pinfunction "C_C") (pintype "passive"))
      (node (ref "RLED") (pin "1") (pinfunction "1_1") (pintype "passive"))
    )
    (net (code "72") (name "Net-(RN1B-1)") (class "Default")
      (node (ref "RN1") (pin "2") (pinfunction "1_2") (pintype "passive"))
      (node (ref "T2") (pin "3") (pinfunction "G_3") (pintype "bidirectional"))
    )
    (net (code "73") (name "Net-(RN1C-1)") (class "Default")
      (node (ref "RN1") (pin "3") (pinfunction "1_3") (pintype "passive"))
      (node (ref "T3") (pin "3") (pinfunction "G_3") (pintype "bidirectional"))
    )
    (net (code "74") (name "Net-(RN1D-1)") (class "Default")
      (node (ref "RN1") (pin "4") (pinfunction "1_4") (pintype "passive"))
      (node (ref "T4") (pin "3") (pinfunction "G_3") (pintype "bidirectional"))
    )
    (net (code "75") (name "Net-(RN2B-1)") (class "Default")
      (node (ref "RN2") (pin "2") (pinfunction "1_2") (pintype "passive"))
      (node (ref "T6") (pin "3") (pinfunction "G_3") (pintype "bidirectional"))
    )
    (net (code "76") (name "Net-(RN2C-1)") (class "Default")
      (node (ref "RN2") (pin "3") (pinfunction "1_3") (pintype "passive"))
      (node (ref "T7") (pin "3") (pinfunction "G_3") (pintype "bidirectional"))
    )
    (net (code "77") (name "Net-(RN2D-1)") (class "Default")
      (node (ref "RN2") (pin "4") (pinfunction "1_4") (pintype "passive"))
      (node (ref "T8") (pin "3") (pinfunction "G_3") (pintype "bidirectional"))
    )
    (net (code "78") (name "Net-(RPI-12-GPIO1)") (class "Default")
      (node (ref "JP4") (pin "12") (pinfunction "12_12") (pintype "passive"))
      (node (ref "RPI") (pin "12") (pinfunction "12-GPIO1_12") (pintype "bidirectional"))
    )
    (net (code "79") (name "Net-(RPI-14-DNC)") (class "Default")
      (node (ref "JP4") (pin "14") (pinfunction "14_14") (pintype "passive"))
      (node (ref "RPI") (pin "14") (pinfunction "14-DNC_14") (pintype "bidirectional"))
    )
    (net (code "80") (name "Net-(RPI-17-DNC)") (class "Default")
      (node (ref "JP4") (pin "17") (pinfunction "17_17") (pintype "passive"))
      (node (ref "RPI") (pin "17") (pinfunction "17-DNC_17") (pintype "bidirectional"))
    )
    (net (code "81") (name "Net-(RPI-18-GPIO5)") (class "Default")
      (node (ref "JP4") (pin "18") (pinfunction "18_18") (pintype "passive"))
      (node (ref "RPI") (pin "18") (pinfunction "18-GPIO5_18") (pintype "bidirectional"))
    )
    (net (code "82") (name "Net-(RPI-19-SPI-MOSI)") (class "Default")
      (node (ref "JP4") (pin "19") (pinfunction "19_19") (pintype "passive"))
      (node (ref "RPI") (pin "19") (pinfunction "19-SPI-MOSI_19") (pintype "bidirectional"))
    )
    (net (code "83") (name "Net-(RPI-20-DNC)") (class "Default")
      (node (ref "JP4") (pin "20") (pinfunction "20_20") (pintype "passive"))
      (node (ref "RPI") (pin "20") (pinfunction "20-DNC_20") (pintype "bidirectional"))
    )
    (net (code "84") (name "Net-(RPI-21-SPI-MISO)") (class "Default")
      (node (ref "JP4") (pin "21") (pinfunction "21_21") (pintype "passive"))
      (node (ref "RPI") (pin "21") (pinfunction "21-SPI-MISO_21") (pintype "bidirectional"))
    )
    (net (code "85") (name "Net-(RPI-22-GPIO6)") (class "Default")
      (node (ref "JP4") (pin "22") (pinfunction "22_22") (pintype "passive"))
      (node (ref "RPI") (pin "22") (pinfunction "22-GPIO6_22") (pintype "bidirectional"))
    )
    (net (code "86") (name "Net-(RPI-23-SPI-SCLK)") (class "Default")
      (node (ref "JP4") (pin "23") (pinfunction "23_23") (pintype "passive"))
      (node (ref "RPI") (pin "23") (pinfunction "23-SPI-SCLK_23") (pintype "bidirectional"))
    )
    (net (code "87") (name "Net-(RPI-24-SPI-CE0-N)") (class "Default")
      (node (ref "JP4") (pin "24") (pinfunction "24_24") (pintype "passive"))
      (node (ref "RPI") (pin "24") (pinfunction "24-SPI-CE0-N_24") (pintype "bidirectional"))
    )
    (net (code "88") (name "Net-(RPI-25-DNC)") (class "Default")
      (node (ref "JP4") (pin "25") (pinfunction "25_25") (pintype "passive"))
      (node (ref "RPI") (pin "25") (pinfunction "25-DNC_25") (pintype "bidirectional"))
    )
    (net (code "89") (name "Net-(RPI-26-SPI-CE1-N)") (class "Default")
      (node (ref "JP4") (pin "26") (pinfunction "26_26") (pintype "passive"))
      (node (ref "RPI") (pin "26") (pinfunction "26-SPI-CE1-N_26") (pintype "bidirectional"))
    )
    (net (code "90") (name "Net-(RPI-27-SD)") (class "Default")
      (node (ref "JP4") (pin "27") (pinfunction "27_27") (pintype "passive"))
      (node (ref "RPI") (pin "27") (pinfunction "27-SD_27") (pintype "bidirectional"))
    )
    (net (code "91") (name "Net-(RPI-28-SC)") (class "Default")
      (node (ref "JP4") (pin "28") (pinfunction "28_28") (pintype "passive"))
      (node (ref "RPI") (pin "28") (pinfunction "28-SC_28") (pintype "bidirectional"))
    )
    (net (code "92") (name "Net-(T1-G)") (class "Default")
      (node (ref "RN1") (pin "1") (pinfunction "1_1") (pintype "passive"))
      (node (ref "T1") (pin "3") (pinfunction "G_3") (pintype "bidirectional"))
    )
    (net (code "93") (name "Net-(T5-G)") (class "Default")
      (node (ref "RN2") (pin "1") (pinfunction "1_1") (pintype "passive"))
      (node (ref "T5") (pin "3") (pinfunction "G_3") (pintype "bidirectional"))
    )
    (net (code "94") (name "Net-(XL2011-VC)") (class "Default")
      (node (ref "C4") (pin "2") (pinfunction "2_2") (pintype "passive"))
      (node (ref "XL2011") (pin "3") (pinfunction "VC_3") (pintype "input"))
    )
    (net (code "95") (name "VCC") (class "Default")
      (node (ref "JP4") (pin "1") (pinfunction "1_1") (pintype "passive"))
      (node (ref "JP6") (pin "1") (pinfunction "1_1") (pintype "passive"))
      (node (ref "JP6") (pin "2") (pinfunction "2_2") (pintype "passive"))
      (node (ref "JP6") (pin "3") (pinfunction "3_3") (pintype "passive"))
      (node (ref "JP6") (pin "4") (pinfunction "4_4") (pintype "passive"))
      (node (ref "RCL") (pin "1") (pinfunction "1_1") (pintype "passive"))
      (node (ref "RDA") (pin "1") (pinfunction "1_1") (pintype "passive"))
      (node (ref "RPI") (pin "1") (pinfunction "1-+3V3_1") (pintype "bidirectional"))
    )
    (net (code "96") (name "unconnected-(U1-ALERT-Pad2)") (class "Default")
      (node (ref "U1") (pin "2") (pinfunction "ALERT_2") (pintype "bidirectional"))
    )
    (net (code "97") (name "unconnected-(U2-ALERT-Pad2)") (class "Default")
      (node (ref "U2") (pin "2") (pinfunction "ALERT_2") (pintype "bidirectional"))
    )
    (net (code "98") (name "unconnected-(XL2011-NC-Pad2)") (class "Default")
      (node (ref "XL2011") (pin "2") (pinfunction "NC_2") (pintype "input"))
    )
  )
)
